# DIABETO_BLE.net
KiCad netlist of a schematic drawn in EAGLE
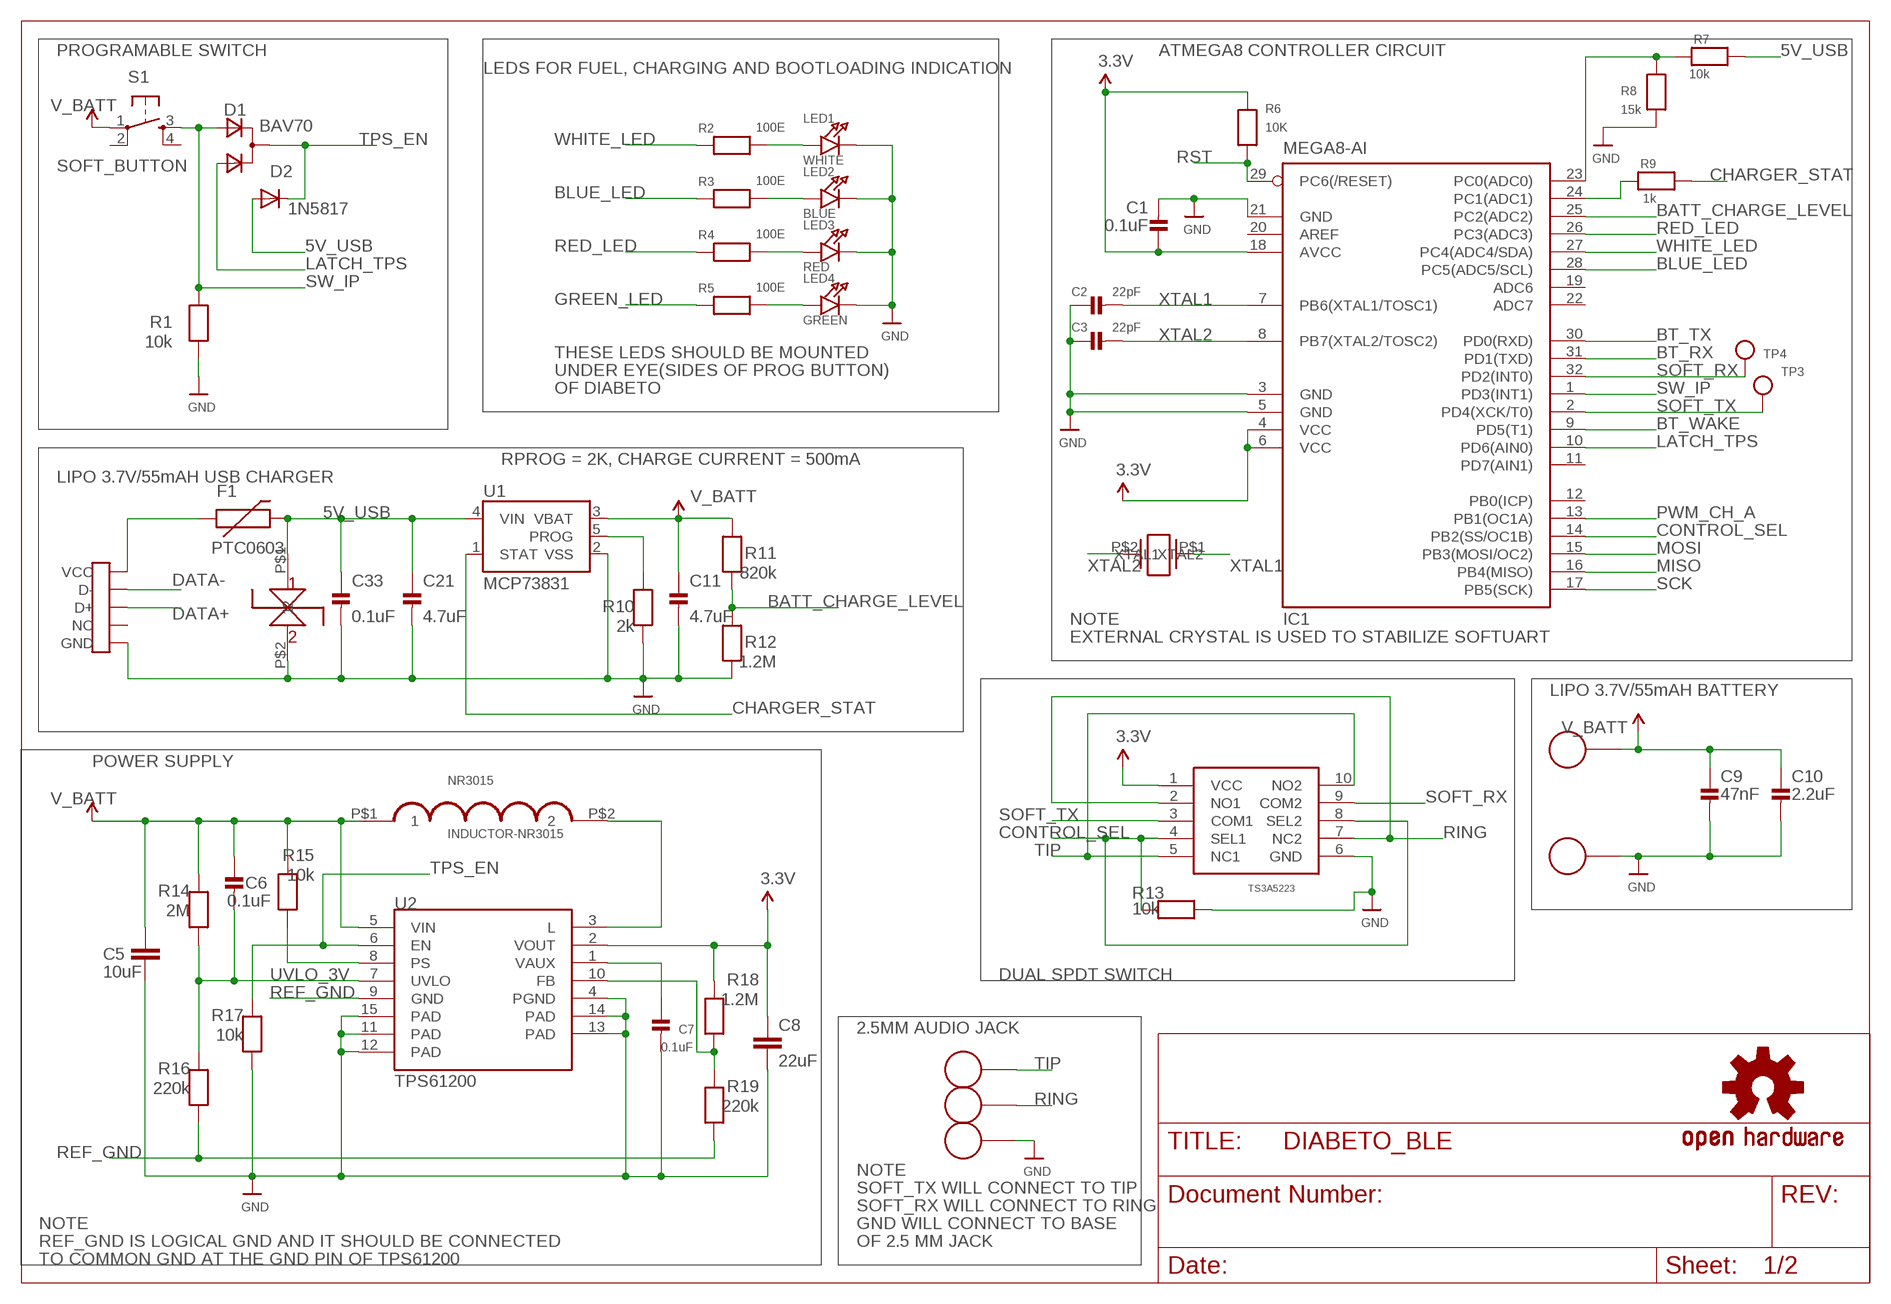
[diagram p0: schematic, sheet 1]
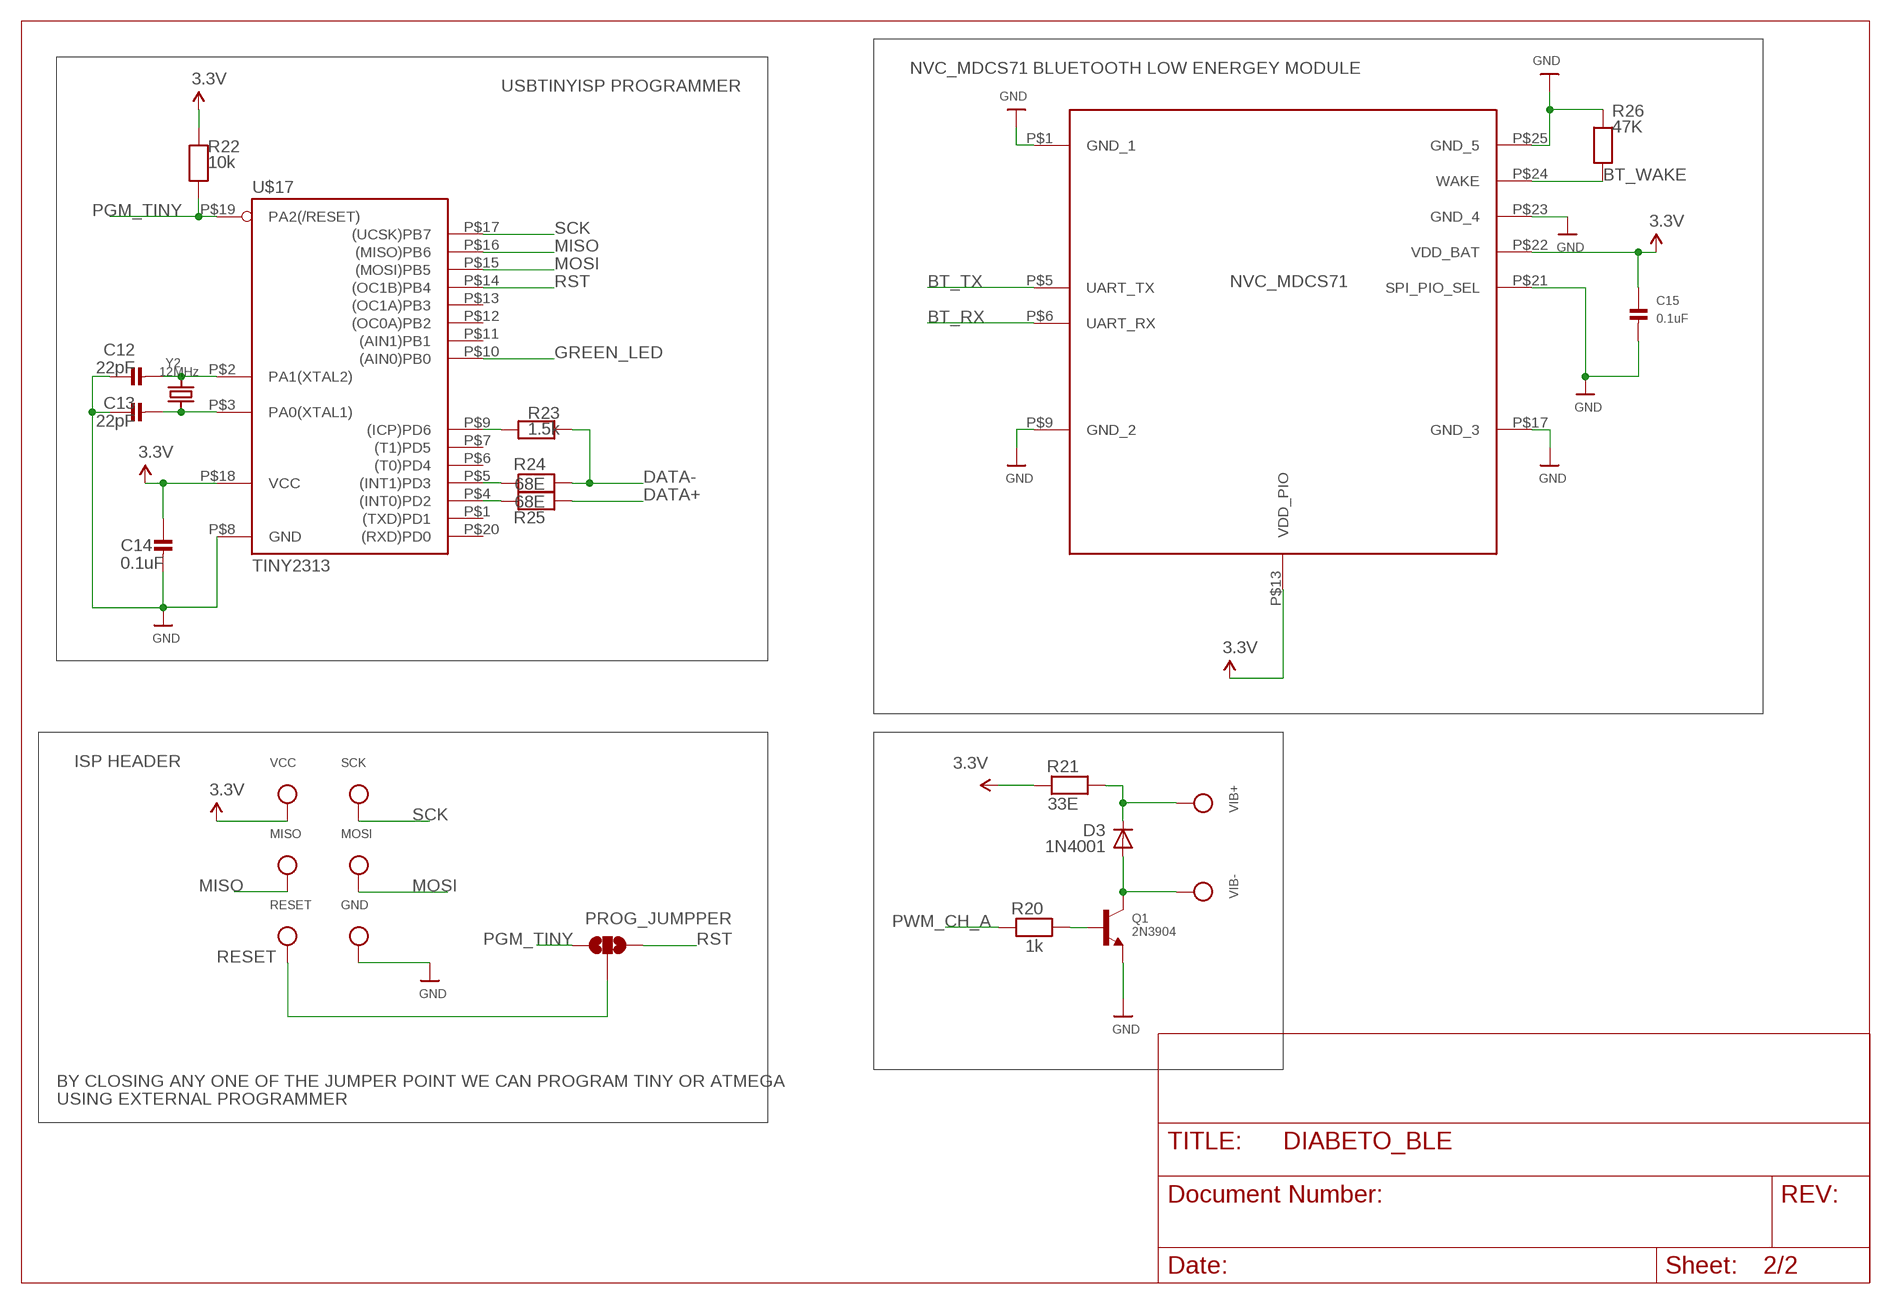
[diagram p1: schematic, sheet 2]

(export (version "E")
  (design (tool "Eeschema 10.0.6"))
  (components
    (comp (ref "C12")
      (value "22pF")
      (footprint "eagle-import:_0402")
      (libsource (lib "eagle-import") (part "CAP_CERAMIC_0402"))
    )
    (comp (ref "C13")
      (value "22pF")
      (footprint "eagle-import:_0402")
      (libsource (lib "eagle-import") (part "CAP_CERAMIC_0402"))
    )
    (comp (ref "C14")
      (value "0.1uF")
      (footprint "eagle-import:_0603")
      (libsource (lib "eagle-import") (part "CAP_CERAMIC_0603"))
    )
    (comp (ref "C15")
      (value "0.1uF")
      (footprint "eagle-import:_0603")
      (libsource (lib "eagle-import") (part "CAP_CERAMIC_0603"))
    )
    (comp (ref "D3")
      (value "1N4001")
      (footprint "eagle-import:SOD-323")
      (libsource (lib "eagle-import") (part "DIODESOD"))
    )
    (comp (ref "GND")
      (value "TESTPOINT0.1\"")
      (footprint "eagle-import:1X01_ROUND")
      (libsource (lib "eagle-import") (part "TESTPOINT0.1{dblquote}"))
    )
    (comp (ref "MISO")
      (value "TESTPOINTROUND1MM")
      (footprint "eagle-import:TESTPOINT_ROUND_1MM")
      (libsource (lib "eagle-import") (part "TESTPOINTROUND1MM"))
    )
    (comp (ref "MOSI")
      (value "TESTPOINTROUND1MM")
      (footprint "eagle-import:TESTPOINT_ROUND_1MM")
      (libsource (lib "eagle-import") (part "TESTPOINTROUND1MM"))
    )
    (comp (ref "PROG_JUMPPER")
      (value "SOLDERJUMPER_2WAY-OLDS")
      (footprint "eagle-import:SJ_3")
      (libsource (lib "eagle-import") (part "SOLDERJUMPER_2WAY-OLDS"))
    )
    (comp (ref "Q1")
      (value "2N3904")
      (footprint "eagle-import:SOT23-R")
      (libsource (lib "eagle-import") (part "TRANSISTOR_NPN"))
    )
    (comp (ref "R20")
      (value "1k")
      (footprint "eagle-import:_0603")
      (libsource (lib "eagle-import") (part "RESISTOR_0603"))
    )
    (comp (ref "R21")
      (value "33E")
      (footprint "eagle-import:_0603")
      (libsource (lib "eagle-import") (part "RESISTOR_0603"))
    )
    (comp (ref "R22")
      (value "10k")
      (footprint "eagle-import:_0603")
      (libsource (lib "eagle-import") (part "RESISTOR_0603"))
    )
    (comp (ref "R23")
      (value "1.5k")
      (footprint "eagle-import:_0603")
      (libsource (lib "eagle-import") (part "RESISTOR_0603"))
    )
    (comp (ref "R24")
      (value "68E")
      (footprint "eagle-import:_0603")
      (libsource (lib "eagle-import") (part "RESISTOR_0603"))
    )
    (comp (ref "R25")
      (value "68E")
      (footprint "eagle-import:_0603")
      (libsource (lib "eagle-import") (part "RESISTOR_0603"))
    )
    (comp (ref "R26")
      (value "47K")
      (footprint "eagle-import:_0603")
      (libsource (lib "eagle-import") (part "RESISTOR_0603"))
    )
    (comp (ref "RESET")
      (value "TESTPOINTROUND1MM")
      (footprint "eagle-import:TESTPOINT_ROUND_1MM")
      (libsource (lib "eagle-import") (part "TESTPOINTROUND1MM"))
    )
    (comp (ref "SCK")
      (value "TESTPOINTROUND1MM")
      (footprint "eagle-import:TESTPOINT_ROUND_1MM")
      (libsource (lib "eagle-import") (part "TESTPOINTROUND1MM"))
    )
    (comp (ref "U$9")
      (value "NVC_MDCS71SMD")
      (footprint "eagle-import:NVC_MDCS71")
      (libsource (lib "eagle-import") (part "NVC_MDCS71SMD"))
    )
    (comp (ref "U$17")
      (value "TINY2313")
      (footprint "eagle-import:MLF20")
      (libsource (lib "eagle-import") (part "TINY2313-M"))
    )
    (comp (ref "VCC")
      (value "TESTPOINT0.1\"")
      (footprint "eagle-import:1X01_ROUND")
      (libsource (lib "eagle-import") (part "TESTPOINT0.1{dblquote}"))
    )
    (comp (ref "VIB+")
      (value "TESTPOINTROUND0.5MM")
      (footprint "eagle-import:TESTPOINT_ROUND_0.5MM")
      (libsource (lib "eagle-import") (part "TESTPOINTROUND0.5MM"))
    )
    (comp (ref "VIB-")
      (value "TESTPOINTROUND0.5MM")
      (footprint "eagle-import:TESTPOINT_ROUND_0.5MM")
      (libsource (lib "eagle-import") (part "TESTPOINTROUND0.5MM"))
    )
    (comp (ref "Y2")
      (value "12MHz")
      (footprint "eagle-import:CRYSTAL_3.2X2.5")
      (libsource (lib "eagle-import") (part "CRYSTALTHIN"))
    )
    (comp (ref "BAT-")
      (value "TIP")
      (footprint "eagle-import:1X01_ROUND")
      (libsource (lib "eagle-import") (part "1X01_ROUND"))
    )
    (comp (ref "C1")
      (value "0.1uF")
      (footprint "eagle-import:_0603")
      (libsource (lib "eagle-import") (part "CAP_CERAMIC_0603"))
    )
    (comp (ref "C2")
      (value "22pF")
      (footprint "eagle-import:_0402")
      (libsource (lib "eagle-import") (part "CAP_CERAMIC_0402"))
    )
    (comp (ref "C3")
      (value "22pF")
      (footprint "eagle-import:_0402")
      (libsource (lib "eagle-import") (part "CAP_CERAMIC_0402"))
    )
    (comp (ref "C5")
      (value "10uF")
      (footprint "eagle-import:1206")
      (libsource (lib "eagle-import") (part "CAP1206"))
    )
    (comp (ref "C6")
      (value "0.1uF")
      (footprint "eagle-import:_0603")
      (libsource (lib "eagle-import") (part "CAP_CERAMIC_0603"))
    )
    (comp (ref "C7")
      (value "0.1uF")
      (footprint "eagle-import:_0603")
      (libsource (lib "eagle-import") (part "CAP_CERAMIC_0603"))
    )
    (comp (ref "C8")
      (value "22uF")
      (footprint "eagle-import:0805")
      (libsource (lib "eagle-import") (part "CAP0805"))
    )
    (comp (ref "C9")
      (value "47nF")
      (footprint "eagle-import:_0603")
      (libsource (lib "eagle-import") (part "CAP_CERAMIC_0603"))
    )
    (comp (ref "C10")
      (value "2.2uF")
      (footprint "eagle-import:_0603")
      (libsource (lib "eagle-import") (part "CAP_CERAMIC_0603"))
    )
    (comp (ref "C11")
      (value "4.7uF")
      (footprint "eagle-import:_0603")
      (libsource (lib "eagle-import") (part "CAP_CERAMIC_0603"))
    )
    (comp (ref "C21")
      (value "4.7uF")
      (footprint "eagle-import:_0603")
      (libsource (lib "eagle-import") (part "CAP_CERAMIC_0603"))
    )
    (comp (ref "C33")
      (value "0.1uF")
      (footprint "eagle-import:_0603")
      (libsource (lib "eagle-import") (part "CAP_CERAMIC_0603"))
    )
    (comp (ref "D1")
      (value "BAV70")
      (footprint "eagle-import:SOT-23")
      (libsource (lib "eagle-import") (part "D_2ASOT23"))
    )
    (comp (ref "D2")
      (value "1N5817")
      (footprint "eagle-import:SOD-123")
      (libsource (lib "eagle-import") (part "DIODESOD-123"))
    )
    (comp (ref "F1")
      (value "PTC0603")
      (footprint "eagle-import:0603")
      (libsource (lib "eagle-import") (part "PTC0603"))
    )
    (comp (ref "IC1")
      (value "MEGA8-AI")
      (footprint "eagle-import:TQFP32-08")
      (fields (field (name "MPN") "ATMEGA8-16AU"))
      (libsource (lib "eagle-import") (part "MEGA8-AI"))
    )
    (comp (ref "LED1")
      (value "WHITE")
      (footprint "eagle-import:CHIPLED_0603")
      (libsource (lib "eagle-import") (part "LED0603"))
    )
    (comp (ref "LED2")
      (value "BLUE")
      (footprint "eagle-import:CHIPLED_0603")
      (libsource (lib "eagle-import") (part "LED0603"))
    )
    (comp (ref "LED3")
      (value "RED")
      (footprint "eagle-import:CHIPLED_0603")
      (libsource (lib "eagle-import") (part "LED0603"))
    )
    (comp (ref "LED4")
      (value "GREEN")
      (footprint "eagle-import:CHIPLED_0603")
      (libsource (lib "eagle-import") (part "LED0603"))
    )
    (comp (ref "NR3015")
      (value "INDUCTOR-NR3015")
      (footprint "eagle-import:INDUCTOR-NR3015")
      (libsource (lib "eagle-import") (part "INDUCTOR-NR3015"))
    )
    (comp (ref "R1")
      (value "10k")
      (footprint "eagle-import:_0603")
      (libsource (lib "eagle-import") (part "RESISTOR_0603"))
    )
    (comp (ref "R2")
      (value "100E")
      (footprint "eagle-import:_0603")
      (libsource (lib "eagle-import") (part "RESISTOR_0603"))
    )
    (comp (ref "R3")
      (value "100E")
      (footprint "eagle-import:_0603")
      (libsource (lib "eagle-import") (part "RESISTOR_0603"))
    )
    (comp (ref "R4")
      (value "100E")
      (footprint "eagle-import:_0603")
      (libsource (lib "eagle-import") (part "RESISTOR_0603"))
    )
    (comp (ref "R5")
      (value "100E")
      (footprint "eagle-import:_0603")
      (libsource (lib "eagle-import") (part "RESISTOR_0603"))
    )
    (comp (ref "R6")
      (value "10K")
      (footprint "eagle-import:_0603")
      (libsource (lib "eagle-import") (part "RESISTOR_0603"))
    )
    (comp (ref "R7")
      (value "10k")
      (footprint "eagle-import:_0603")
      (libsource (lib "eagle-import") (part "RESISTOR_0603"))
    )
    (comp (ref "R8")
      (value "15k")
      (footprint "eagle-import:_0603")
      (libsource (lib "eagle-import") (part "RESISTOR_0603"))
    )
    (comp (ref "R9")
      (value "1k")
      (footprint "eagle-import:_0603")
      (libsource (lib "eagle-import") (part "RESISTOR_0603"))
    )
    (comp (ref "R10")
      (value "2k")
      (footprint "eagle-import:_0603")
      (libsource (lib "eagle-import") (part "RESISTOR_0603"))
    )
    (comp (ref "R11")
      (value "820k")
      (footprint "eagle-import:_0603")
      (libsource (lib "eagle-import") (part "RESISTOR_0603"))
    )
    (comp (ref "R12")
      (value "1.2M")
      (footprint "eagle-import:_0603")
      (libsource (lib "eagle-import") (part "RESISTOR_0603"))
    )
    (comp (ref "R13")
      (value "10k")
      (footprint "eagle-import:_0603")
      (libsource (lib "eagle-import") (part "RESISTOR_0603"))
    )
    (comp (ref "R14")
      (value "2M")
      (footprint "eagle-import:_0603")
      (libsource (lib "eagle-import") (part "RESISTOR_0603"))
    )
    (comp (ref "R15")
      (value "10k")
      (footprint "eagle-import:_0603")
      (libsource (lib "eagle-import") (part "RESISTOR_0603"))
    )
    (comp (ref "R16")
      (value "220k")
      (footprint "eagle-import:_0603")
      (libsource (lib "eagle-import") (part "RESISTOR_0603"))
    )
    (comp (ref "R17")
      (value "10k")
      (footprint "eagle-import:_0603")
      (libsource (lib "eagle-import") (part "RESISTOR_0603"))
    )
    (comp (ref "R18")
      (value "1.2M")
      (footprint "eagle-import:_0603")
      (libsource (lib "eagle-import") (part "RESISTOR_0603"))
    )
    (comp (ref "R19")
      (value "220k")
      (footprint "eagle-import:_0603")
      (libsource (lib "eagle-import") (part "RESISTOR_0603"))
    )
    (comp (ref "S1")
      (value "SOFT_BUTTON")
      (footprint "eagle-import:TACTILE_SWITCH_SMD")
      (libsource (lib "eagle-import") (part "TAC_SWITCHSMD"))
    )
    (comp (ref "TIP")
      (value "TIP")
      (footprint "eagle-import:1X01_ROUND")
      (libsource (lib "eagle-import") (part "1X01_ROUND"))
    )
    (comp (ref "TIP1")
      (value "TIP")
      (footprint "eagle-import:1X01_ROUND")
      (libsource (lib "eagle-import") (part "1X01_ROUND"))
    )
    (comp (ref "TP3")
      (value "TESTPOINTROUND1MM")
      (footprint "eagle-import:TESTPOINT_ROUND_1MM")
      (libsource (lib "eagle-import") (part "TESTPOINTROUND1MM"))
    )
    (comp (ref "TP4")
      (value "TESTPOINTROUND1MM")
      (footprint "eagle-import:TESTPOINT_ROUND_1MM")
      (libsource (lib "eagle-import") (part "TESTPOINTROUND1MM"))
    )
    (comp (ref "U$2")
      (value "MICRO_USB_DIABETOMICRO_USB_SMD")
      (footprint "eagle-import:MICRO_USB_DIABETO")
      (libsource (lib "eagle-import") (part "MICRO_USB_DIABETOMICRO_USB_SMD"))
    )
    (comp (ref "U$4")
      (value "TVS_DIODE")
      (footprint "eagle-import:0603")
      (libsource (lib "eagle-import") (part "TVS_DIODE"))
    )
    (comp (ref "U$20")
      (value "TS3A5223")
      (footprint "eagle-import:TS3A5223-QFN")
      (libsource (lib "eagle-import") (part "TS3A5223"))
    )
    (comp (ref "U$21")
      (value "OSHW-LOGOS")
      (footprint "eagle-import:OSHW-LOGO-S")
      (libsource (lib "eagle-import") (part "OSHW-LOGOS"))
    )
    (comp (ref "U$23")
      (value "8MHZ")
      (footprint "eagle-import:5X3.2_2PAD")
      (libsource (lib "eagle-import") (part "NX5032GA"))
    )
    (comp (ref "U$26")
      (value "1X01_ROUND")
      (footprint "eagle-import:1X01_ROUND")
      (libsource (lib "eagle-import") (part "1X01_ROUND"))
    )
    (comp (ref "U$28")
      (value "1X01_ROUND")
      (footprint "eagle-import:1X01_ROUND")
      (libsource (lib "eagle-import") (part "1X01_ROUND"))
    )
    (comp (ref "U1")
      (value "MCP73831")
      (footprint "eagle-import:SOT23-5")
      (libsource (lib "eagle-import") (part "MCP73831"))
    )
    (comp (ref "U2")
      (value "TPS61200")
      (footprint "eagle-import:QFN-10_PAD")
      (libsource (lib "eagle-import") (part "TPS61200"))
    )
  )
  (nets
    (net (code "1") (name "3.3V") (class "Default")
      (node (ref "C1") (pin "1") (pinfunction "P$1_1") (pintype "passive"))
      (node (ref "C14") (pin "1") (pinfunction "P$1_1") (pintype "passive"))
      (node (ref "C15") (pin "1") (pinfunction "P$1_1") (pintype "passive"))
      (node (ref "C8") (pin "1") (pinfunction "1_1") (pintype "passive"))
      (node (ref "IC1") (pin "18") (pinfunction "AVCC_18") (pintype "power_in"))
      (node (ref "IC1") (pin "4") (pinfunction "VCC_4") (pintype "power_in"))
      (node (ref "IC1") (pin "6") (pinfunction "VCC_6") (pintype "power_in"))
      (node (ref "R18") (pin "2") (pinfunction "2_2") (pintype "passive"))
      (node (ref "R21") (pin "1") (pinfunction "1_1") (pintype "passive"))
      (node (ref "R22") (pin "1") (pinfunction "1_1") (pintype "passive"))
      (node (ref "R6") (pin "2") (pinfunction "2_2") (pintype "passive"))
      (node (ref "U$17") (pin "P$18") (pinfunction "VCC_P$18") (pintype "power_in"))
      (node (ref "U$20") (pin "1") (pinfunction "VCC_1") (pintype "bidirectional"))
      (node (ref "U$9") (pin "P$13") (pinfunction "VDD_PIO_P$13") (pintype "bidirectional"))
      (node (ref "U$9") (pin "P$22") (pinfunction "VDD_BAT_P$22") (pintype "bidirectional"))
      (node (ref "U2") (pin "2") (pinfunction "VOUT_2") (pintype "passive"))
      (node (ref "VCC") (pin "1") (pinfunction "P$1_1") (pintype "bidirectional"))
    )
    (net (code "2") (name "5V_USB") (class "Default")
      (node (ref "C21") (pin "1") (pinfunction "P$1_1") (pintype "passive"))
      (node (ref "C33") (pin "1") (pinfunction "P$1_1") (pintype "passive"))
      (node (ref "D2") (pin "A") (pinfunction "A_A") (pintype "passive"))
      (node (ref "F1") (pin "2") (pinfunction "2_2") (pintype "bidirectional"))
      (node (ref "R7") (pin "1") (pinfunction "1_1") (pintype "passive"))
      (node (ref "U$4") (pin "P$1") (pinfunction "1_P$1") (pintype "bidirectional"))
      (node (ref "U1") (pin "4") (pinfunction "VIN_4") (pintype "power_in"))
    )
    (net (code "3") (name "BATT_CHARGE_LEVEL") (class "Default")
      (node (ref "IC1") (pin "25") (pinfunction "PC2(ADC2)_25") (pintype "bidirectional"))
      (node (ref "R11") (pin "1") (pinfunction "1_1") (pintype "passive"))
      (node (ref "R12") (pin "2") (pinfunction "2_2") (pintype "passive"))
    )
    (net (code "4") (name "BLUE_LED") (class "Default")
      (node (ref "IC1") (pin "28") (pinfunction "PC5(ADC5/SCL)_28") (pintype "bidirectional"))
      (node (ref "R3") (pin "2") (pinfunction "2_2") (pintype "passive"))
    )
    (net (code "5") (name "BT_RX") (class "Default")
      (node (ref "IC1") (pin "31") (pinfunction "PD1(TXD)_31") (pintype "bidirectional"))
      (node (ref "U$9") (pin "P$6") (pinfunction "UART_RX_P$6") (pintype "bidirectional"))
    )
    (net (code "6") (name "BT_TX") (class "Default")
      (node (ref "IC1") (pin "30") (pinfunction "PD0(RXD)_30") (pintype "bidirectional"))
      (node (ref "U$9") (pin "P$5") (pinfunction "UART_TX_P$5") (pintype "bidirectional"))
    )
    (net (code "7") (name "BT_WAKE") (class "Default")
      (node (ref "IC1") (pin "9") (pinfunction "PD5(T1)_9") (pintype "bidirectional"))
      (node (ref "R26") (pin "2") (pinfunction "2_2") (pintype "passive"))
      (node (ref "U$9") (pin "P$24") (pinfunction "WAKE_P$24") (pintype "bidirectional"))
    )
    (net (code "8") (name "CHARGER_STAT") (class "Default")
      (node (ref "R9") (pin "1") (pinfunction "1_1") (pintype "passive"))
      (node (ref "U1") (pin "1") (pinfunction "STAT_1") (pintype "output"))
    )
    (net (code "9") (name "CONTROL_SEL") (class "Default")
      (node (ref "IC1") (pin "14") (pinfunction "PB2(SS/OC1B)_14") (pintype "bidirectional"))
      (node (ref "R13") (pin "2") (pinfunction "2_2") (pintype "passive"))
      (node (ref "U$20") (pin "4") (pinfunction "SEL1_4") (pintype "bidirectional"))
      (node (ref "U$20") (pin "8") (pinfunction "SEL2_8") (pintype "bidirectional"))
    )
    (net (code "10") (name "DATA+") (class "Default")
      (node (ref "R25") (pin "2") (pinfunction "2_2") (pintype "passive"))
      (node (ref "U$2") (pin "P$3") (pinfunction "D+_P$3") (pintype "bidirectional"))
    )
    (net (code "11") (name "DATA-") (class "Default")
      (node (ref "R23") (pin "1") (pinfunction "1_1") (pintype "passive"))
      (node (ref "R24") (pin "2") (pinfunction "2_2") (pintype "passive"))
      (node (ref "U$2") (pin "P$6") (pinfunction "D-_P$6") (pintype "bidirectional"))
    )
    (net (code "12") (name "GND") (class "Default")
      (node (ref "BAT-") (pin "P$1") (pinfunction "1_P$1") (pintype "bidirectional"))
      (node (ref "C1") (pin "2") (pinfunction "P$2_2") (pintype "passive"))
      (node (ref "C10") (pin "2") (pinfunction "P$2_2") (pintype "passive"))
      (node (ref "C11") (pin "2") (pinfunction "P$2_2") (pintype "passive"))
      (node (ref "C12") (pin "1") (pinfunction "P$1_1") (pintype "passive"))
      (node (ref "C13") (pin "1") (pinfunction "P$1_1") (pintype "passive"))
      (node (ref "C14") (pin "2") (pinfunction "P$2_2") (pintype "passive"))
      (node (ref "C15") (pin "2") (pinfunction "P$2_2") (pintype "passive"))
      (node (ref "C2") (pin "1") (pinfunction "P$1_1") (pintype "passive"))
      (node (ref "C21") (pin "2") (pinfunction "P$2_2") (pintype "passive"))
      (node (ref "C3") (pin "1") (pinfunction "P$1_1") (pintype "passive"))
      (node (ref "C33") (pin "2") (pinfunction "P$2_2") (pintype "passive"))
      (node (ref "C5") (pin "2") (pinfunction "2_2") (pintype "passive"))
      (node (ref "C7") (pin "2") (pinfunction "P$2_2") (pintype "passive"))
      (node (ref "C8") (pin "2") (pinfunction "2_2") (pintype "passive"))
      (node (ref "C9") (pin "2") (pinfunction "P$2_2") (pintype "passive"))
      (node (ref "GND") (pin "1") (pinfunction "P$1_1") (pintype "bidirectional"))
      (node (ref "IC1") (pin "21") (pinfunction "GND_21") (pintype "power_in"))
      (node (ref "IC1") (pin "3") (pinfunction "GND_3") (pintype "power_in"))
      (node (ref "IC1") (pin "5") (pinfunction "GND_5") (pintype "power_in"))
      (node (ref "LED1") (pin "C") (pinfunction "C_C") (pintype "passive"))
      (node (ref "LED2") (pin "C") (pinfunction "C_C") (pintype "passive"))
      (node (ref "LED3") (pin "C") (pinfunction "C_C") (pintype "passive"))
      (node (ref "LED4") (pin "C") (pinfunction "C_C") (pintype "passive"))
      (node (ref "Q1") (pin "2") (pinfunction "E_2") (pintype "passive"))
      (node (ref "R1") (pin "1") (pinfunction "1_1") (pintype "passive"))
      (node (ref "R10") (pin "1") (pinfunction "1_1") (pintype "passive"))
      (node (ref "R12") (pin "1") (pinfunction "1_1") (pintype "passive"))
      (node (ref "R13") (pin "1") (pinfunction "1_1") (pintype "passive"))
      (node (ref "R17") (pin "1") (pinfunction "1_1") (pintype "passive"))
      (node (ref "R26") (pin "1") (pinfunction "1_1") (pintype "passive"))
      (node (ref "R8") (pin "2") (pinfunction "2_2") (pintype "passive"))
      (node (ref "U$17") (pin "P$8") (pinfunction "GND_P$8") (pintype "power_in"))
      (node (ref "U$2") (pin "P$5") (pinfunction "GND_P$5") (pintype "bidirectional"))
      (node (ref "U$20") (pin "6") (pinfunction "GND_6") (pintype "bidirectional"))
      (node (ref "U$28") (pin "P$1") (pinfunction "1_P$1") (pintype "bidirectional"))
      (node (ref "U$4") (pin "P$2") (pinfunction "2_P$2") (pintype "bidirectional"))
      (node (ref "U$9") (pin "P$1") (pinfunction "GND_1_P$1") (pintype "bidirectional"))
      (node (ref "U$9") (pin "P$17") (pinfunction "GND_3_P$17") (pintype "bidirectional"))
      (node (ref "U$9") (pin "P$21") (pinfunction "SPI_PIO_SEL_P$21") (pintype "bidirectional"))
      (node (ref "U$9") (pin "P$23") (pinfunction "GND_4_P$23") (pintype "bidirectional"))
      (node (ref "U$9") (pin "P$25") (pinfunction "GND_5_P$25") (pintype "bidirectional"))
      (node (ref "U$9") (pin "P$9") (pinfunction "GND_2_P$9") (pintype "bidirectional"))
      (node (ref "U1") (pin "2") (pinfunction "VSS_2") (pintype "power_in"))
      (node (ref "U2") (pin "11") (pinfunction "PAD_11") (pintype "power_in"))
      (node (ref "U2") (pin "12") (pinfunction "PAD_12") (pintype "power_in"))
      (node (ref "U2") (pin "13") (pinfunction "PAD_13") (pintype "power_in"))
      (node (ref "U2") (pin "14") (pinfunction "PAD_14") (pintype "power_in"))
      (node (ref "U2") (pin "15") (pinfunction "PAD_15") (pintype "power_in"))
      (node (ref "U2") (pin "4") (pinfunction "PGND_4") (pintype "power_in"))
    )
    (net (code "13") (name "GREEN_LED") (class "Default")
      (node (ref "R5") (pin "2") (pinfunction "2_2") (pintype "passive"))
      (node (ref "U$17") (pin "P$10") (pinfunction "(AIN0)PB0_P$10") (pintype "bidirectional"))
    )
    (net (code "14") (name "LATCH_TPS") (class "Default")
      (node (ref "D1") (pin "3") (pinfunction "A2_3") (pintype "passive"))
      (node (ref "IC1") (pin "10") (pinfunction "PD6(AIN0)_10") (pintype "bidirectional"))
    )
    (net (code "15") (name "MISO") (class "Default")
      (node (ref "IC1") (pin "16") (pinfunction "PB4(MISO)_16") (pintype "bidirectional"))
      (node (ref "MISO") (pin "P$1") (pinfunction "P$1_P$1") (pintype "bidirectional"))
      (node (ref "U$17") (pin "P$16") (pinfunction "(MISO)PB6_P$16") (pintype "bidirectional"))
    )
    (net (code "16") (name "MOSI") (class "Default")
      (node (ref "IC1") (pin "15") (pinfunction "PB3(MOSI/OC2)_15") (pintype "bidirectional"))
      (node (ref "MOSI") (pin "P$1") (pinfunction "P$1_P$1") (pintype "bidirectional"))
      (node (ref "U$17") (pin "P$15") (pinfunction "(MOSI)PB5_P$15") (pintype "bidirectional"))
    )
    (net (code "17") (name "Net-(C7-P$1)") (class "Default")
      (node (ref "C7") (pin "1") (pinfunction "P$1_1") (pintype "passive"))
      (node (ref "U2") (pin "1") (pinfunction "VAUX_1") (pintype "passive"))
    )
    (net (code "18") (name "Net-(C12-P$2)") (class "Default")
      (node (ref "C12") (pin "2") (pinfunction "P$2_2") (pintype "passive"))
      (node (ref "U$17") (pin "P$2") (pinfunction "PA1(XTAL2)_P$2") (pintype "bidirectional"))
      (node (ref "Y2") (pin "2") (pinfunction "2_2") (pintype "passive"))
    )
    (net (code "19") (name "Net-(C13-P$2)") (class "Default")
      (node (ref "C13") (pin "2") (pinfunction "P$2_2") (pintype "passive"))
      (node (ref "U$17") (pin "P$3") (pinfunction "PA0(XTAL1)_P$3") (pintype "bidirectional"))
      (node (ref "Y2") (pin "1") (pinfunction "1_1") (pintype "passive"))
    )
    (net (code "20") (name "Net-(D3-A)") (class "Default")
      (node (ref "D3") (pin "2") (pinfunction "A_2") (pintype "passive"))
      (node (ref "Q1") (pin "3") (pinfunction "C_3") (pintype "passive"))
      (node (ref "VIB-") (pin "P$1") (pinfunction "P$1_P$1") (pintype "bidirectional"))
    )
    (net (code "21") (name "Net-(D3-C)") (class "Default")
      (node (ref "D3") (pin "1") (pinfunction "C_1") (pintype "passive"))
      (node (ref "R21") (pin "2") (pinfunction "2_2") (pintype "passive"))
      (node (ref "VIB+") (pin "P$1") (pinfunction "P$1_P$1") (pintype "bidirectional"))
    )
    (net (code "22") (name "Net-(IC1-PC0(ADC0))") (class "Default")
      (node (ref "IC1") (pin "23") (pinfunction "PC0(ADC0)_23") (pintype "bidirectional"))
      (node (ref "R7") (pin "2") (pinfunction "2_2") (pintype "passive"))
      (node (ref "R8") (pin "1") (pinfunction "1_1") (pintype "passive"))
    )
    (net (code "23") (name "Net-(IC1-PC1(ADC1))") (class "Default")
      (node (ref "IC1") (pin "24") (pinfunction "PC1(ADC1)_24") (pintype "bidirectional"))
      (node (ref "R9") (pin "2") (pinfunction "2_2") (pintype "passive"))
    )
    (net (code "24") (name "Net-(LED1-PadA)") (class "Default")
      (node (ref "LED1") (pin "A") (pinfunction "A_A") (pintype "passive"))
      (node (ref "R2") (pin "1") (pinfunction "1_1") (pintype "passive"))
    )
    (net (code "25") (name "Net-(LED2-PadA)") (class "Default")
      (node (ref "LED2") (pin "A") (pinfunction "A_A") (pintype "passive"))
      (node (ref "R3") (pin "1") (pinfunction "1_1") (pintype "passive"))
    )
    (net (code "26") (name "Net-(LED3-PadA)") (class "Default")
      (node (ref "LED3") (pin "A") (pinfunction "A_A") (pintype "passive"))
      (node (ref "R4") (pin "1") (pinfunction "1_1") (pintype "passive"))
    )
    (net (code "27") (name "Net-(LED4-PadA)") (class "Default")
      (node (ref "LED4") (pin "A") (pinfunction "A_A") (pintype "passive"))
      (node (ref "R5") (pin "1") (pinfunction "1_1") (pintype "passive"))
    )
    (net (code "28") (name "Net-(NR3015-2)") (class "Default")
      (node (ref "NR3015") (pin "P$2") (pinfunction "2_P$2") (pintype "bidirectional"))
      (node (ref "U2") (pin "3") (pinfunction "L_3") (pintype "passive"))
    )
    (net (code "29") (name "Net-(Q1-B)") (class "Default")
      (node (ref "Q1") (pin "1") (pinfunction "B_1") (pintype "passive"))
      (node (ref "R20") (pin "2") (pinfunction "2_2") (pintype "passive"))
    )
    (net (code "30") (name "Net-(U$2-VCC)") (class "Default")
      (node (ref "F1") (pin "1") (pinfunction "1_1") (pintype "bidirectional"))
      (node (ref "U$2") (pin "P$7") (pinfunction "VCC_P$7") (pintype "bidirectional"))
    )
    (net (code "31") (name "Net-(U$17-(ICP)PD6)") (class "Default")
      (node (ref "R23") (pin "2") (pinfunction "2_2") (pintype "passive"))
      (node (ref "U$17") (pin "P$9") (pinfunction "(ICP)PD6_P$9") (pintype "bidirectional"))
    )
    (net (code "32") (name "Net-(U$17-(INT0)PD2)") (class "Default")
      (node (ref "R25") (pin "1") (pinfunction "1_1") (pintype "passive"))
      (node (ref "U$17") (pin "P$4") (pinfunction "(INT0)PD2_P$4") (pintype "bidirectional"))
    )
    (net (code "33") (name "Net-(U$17-(INT1)PD3)") (class "Default")
      (node (ref "R24") (pin "1") (pinfunction "1_1") (pintype "passive"))
      (node (ref "U$17") (pin "P$5") (pinfunction "(INT1)PD3_P$5") (pintype "bidirectional"))
    )
    (net (code "34") (name "Net-(U1-PROG)") (class "Default")
      (node (ref "R10") (pin "2") (pinfunction "2_2") (pintype "passive"))
      (node (ref "U1") (pin "5") (pinfunction "PROG_5") (pintype "input"))
    )
    (net (code "35") (name "Net-(U2-FB)") (class "Default")
      (node (ref "R18") (pin "1") (pinfunction "1_1") (pintype "passive"))
      (node (ref "R19") (pin "2") (pinfunction "2_2") (pintype "passive"))
      (node (ref "U2") (pin "10") (pinfunction "FB_10") (pintype "passive"))
    )
    (net (code "36") (name "Net-(U2-PS)") (class "Default")
      (node (ref "R15") (pin "1") (pinfunction "1_1") (pintype "passive"))
      (node (ref "U2") (pin "8") (pinfunction "PS_8") (pintype "input"))
    )
    (net (code "37") (name "PGM_TINY") (class "Default")
      (node (ref "PROG_JUMPPER") (pin "1") (pinfunction "1_1") (pintype "passive"))
      (node (ref "R22") (pin "2") (pinfunction "2_2") (pintype "passive"))
      (node (ref "U$17") (pin "P$19") (pinfunction "PA2(/RESET)_P$19") (pintype "input"))
    )
    (net (code "38") (name "PWM_CH_A") (class "Default")
      (node (ref "IC1") (pin "13") (pinfunction "PB1(OC1A)_13") (pintype "bidirectional"))
      (node (ref "R20") (pin "1") (pinfunction "1_1") (pintype "passive"))
    )
    (net (code "39") (name "RED_LED") (class "Default")
      (node (ref "IC1") (pin "26") (pinfunction "PC3(ADC3)_26") (pintype "bidirectional"))
      (node (ref "R4") (pin "2") (pinfunction "2_2") (pintype "passive"))
    )
    (net (code "40") (name "REF_GND") (class "Default")
      (node (ref "R16") (pin "1") (pinfunction "1_1") (pintype "passive"))
      (node (ref "R19") (pin "1") (pinfunction "1_1") (pintype "passive"))
      (node (ref "U2") (pin "9") (pinfunction "GND_9") (pintype "power_in"))
    )
    (net (code "41") (name "RESET") (class "Default")
      (node (ref "PROG_JUMPPER") (pin "2") (pinfunction "2_2") (pintype "passive"))
      (node (ref "RESET") (pin "P$1") (pinfunction "P$1_P$1") (pintype "bidirectional"))
    )
    (net (code "42") (name "RING") (class "Default")
      (node (ref "U$20") (pin "2") (pinfunction "NO1_2") (pintype "bidirectional"))
      (node (ref "U$20") (pin "7") (pinfunction "NC2_7") (pintype "bidirectional"))
      (node (ref "U$26") (pin "P$1") (pinfunction "1_P$1") (pintype "bidirectional"))
    )
    (net (code "43") (name "RST") (class "Default")
      (node (ref "IC1") (pin "29") (pinfunction "PC6(/RESET)_29") (pintype "bidirectional"))
      (node (ref "PROG_JUMPPER") (pin "3") (pinfunction "3_3") (pintype "passive"))
      (node (ref "R6") (pin "1") (pinfunction "1_1") (pintype "passive"))
      (node (ref "U$17") (pin "P$14") (pinfunction "(OC1B)PB4_P$14") (pintype "bidirectional"))
    )
    (net (code "44") (name "SCK") (class "Default")
      (node (ref "IC1") (pin "17") (pinfunction "PB5(SCK)_17") (pintype "bidirectional"))
      (node (ref "SCK") (pin "P$1") (pinfunction "P$1_P$1") (pintype "bidirectional"))
      (node (ref "U$17") (pin "P$17") (pinfunction "(UCSK)PB7_P$17") (pintype "bidirectional"))
    )
    (net (code "45") (name "SOFT_RX") (class "Default")
      (node (ref "IC1") (pin "32") (pinfunction "PD2(INT0)_32") (pintype "bidirectional"))
      (node (ref "TP4") (pin "P$1") (pinfunction "P$1_P$1") (pintype "bidirectional"))
      (node (ref "U$20") (pin "9") (pinfunction "COM2_9") (pintype "bidirectional"))
    )
    (net (code "46") (name "SOFT_TX") (class "Default")
      (node (ref "IC1") (pin "2") (pinfunction "PD4(XCK/T0)_2") (pintype "bidirectional"))
      (node (ref "TP3") (pin "P$1") (pinfunction "P$1_P$1") (pintype "bidirectional"))
      (node (ref "U$20") (pin "3") (pinfunction "COM1_3") (pintype "bidirectional"))
    )
    (net (code "47") (name "SW_IP") (class "Default")
      (node (ref "D1") (pin "2") (pinfunction "A1_2") (pintype "passive"))
      (node (ref "IC1") (pin "1") (pinfunction "PD3(INT1)_1") (pintype "bidirectional"))
      (node (ref "R1") (pin "2") (pinfunction "2_2") (pintype "passive"))
      (node (ref "S1") (pin "3") (pinfunction "3_3") (pintype "passive"))
    )
    (net (code "48") (name "TIP") (class "Default")
      (node (ref "TIP") (pin "P$1") (pinfunction "1_P$1") (pintype "bidirectional"))
      (node (ref "U$20") (pin "10") (pinfunction "NO2_10") (pintype "bidirectional"))
      (node (ref "U$20") (pin "5") (pinfunction "NC1_5") (pintype "bidirectional"))
    )
    (net (code "49") (name "TPS_EN") (class "Default")
      (node (ref "D1") (pin "1") (pinfunction "C_1") (pintype "passive"))
      (node (ref "D2") (pin "C") (pinfunction "C_C") (pintype "passive"))
      (node (ref "R17") (pin "2") (pinfunction "2_2") (pintype "passive"))
      (node (ref "U2") (pin "6") (pinfunction "EN_6") (pintype "input"))
    )
    (net (code "50") (name "UVLO_3V") (class "Default")
      (node (ref "C6") (pin "2") (pinfunction "P$2_2") (pintype "passive"))
      (node (ref "R14") (pin "1") (pinfunction "1_1") (pintype "passive"))
      (node (ref "R16") (pin "2") (pinfunction "2_2") (pintype "passive"))
      (node (ref "U2") (pin "7") (pinfunction "UVLO_7") (pintype "passive"))
    )
    (net (code "51") (name "V_BATT") (class "Default")
      (node (ref "C10") (pin "1") (pinfunction "P$1_1") (pintype "passive"))
      (node (ref "C11") (pin "1") (pinfunction "P$1_1") (pintype "passive"))
      (node (ref "C5") (pin "1") (pinfunction "1_1") (pintype "passive"))
      (node (ref "C6") (pin "1") (pinfunction "P$1_1") (pintype "passive"))
      (node (ref "C9") (pin "1") (pinfunction "P$1_1") (pintype "passive"))
      (node (ref "NR3015") (pin "P$1") (pinfunction "1_P$1") (pintype "bidirectional"))
      (node (ref "R11") (pin "2") (pinfunction "2_2") (pintype "passive"))
      (node (ref "R14") (pin "2") (pinfunction "2_2") (pintype "passive"))
      (node (ref "R15") (pin "2") (pinfunction "2_2") (pintype "passive"))
      (node (ref "S1") (pin "1") (pinfunction "1_1") (pintype "passive"))
      (node (ref "TIP1") (pin "P$1") (pinfunction "1_P$1") (pintype "bidirectional"))
      (node (ref "U1") (pin "3") (pinfunction "VBAT_3") (pintype "power_in"))
      (node (ref "U2") (pin "5") (pinfunction "VIN_5") (pintype "power_in"))
    )
    (net (code "52") (name "WHITE_LED") (class "Default")
      (node (ref "IC1") (pin "27") (pinfunction "PC4(ADC4/SDA)_27") (pintype "bidirectional"))
      (node (ref "R2") (pin "2") (pinfunction "2_2") (pintype "passive"))
    )
    (net (code "53") (name "XTAL1") (class "Default")
      (node (ref "C2") (pin "2") (pinfunction "P$2_2") (pintype "passive"))
      (node (ref "IC1") (pin "7") (pinfunction "PB6(XTAL1/TOSC1)_7") (pintype "bidirectional"))
      (node (ref "U$23") (pin "P$1") (pinfunction "XTAL1_P$1") (pintype "bidirectional"))
    )
    (net (code "54") (name "XTAL2") (class "Default")
      (node (ref "C3") (pin "2") (pinfunction "P$2_2") (pintype "passive"))
      (node (ref "IC1") (pin "8") (pinfunction "PB7(XTAL2/TOSC2)_8") (pintype "bidirectional"))
      (node (ref "U$23") (pin "P$2") (pinfunction "XTAL2_P$2") (pintype "bidirectional"))
    )
    (net (code "55") (name "unconnected-(IC1-ADC6-Pad19)") (class "Default")
      (node (ref "IC1") (pin "19") (pinfunction "ADC6_19") (pintype "bidirectional"))
    )
    (net (code "56") (name "unconnected-(IC1-ADC7-Pad22)") (class "Default")
      (node (ref "IC1") (pin "22") (pinfunction "ADC7_22") (pintype "bidirectional"))
    )
    (net (code "57") (name "unconnected-(IC1-AREF-Pad20)") (class "Default")
      (node (ref "IC1") (pin "20") (pinfunction "AREF_20") (pintype "passive"))
    )
    (net (code "58") (name "unconnected-(IC1-PB0(ICP)-Pad12)") (class "Default")
      (node (ref "IC1") (pin "12") (pinfunction "PB0(ICP)_12") (pintype "bidirectional"))
    )
    (net (code "59") (name "unconnected-(IC1-PD7(AIN1)-Pad11)") (class "Default")
      (node (ref "IC1") (pin "11") (pinfunction "PD7(AIN1)_11") (pintype "bidirectional"))
    )
    (net (code "60") (name "unconnected-(S1-Pad2)") (class "Default")
      (node (ref "S1") (pin "2") (pinfunction "2_2") (pintype "passive"))
    )
    (net (code "61") (name "unconnected-(S1-Pad4)") (class "Default")
      (node (ref "S1") (pin "4") (pinfunction "4_4") (pintype "passive"))
    )
    (net (code "62") (name "unconnected-(U$2-NC-PadP$4)") (class "Default")
      (node (ref "U$2") (pin "P$4") (pinfunction "NC_P$4") (pintype "bidirectional"))
    )
    (net (code "63") (name "unconnected-(U$17-(AIN1)PB1-PadP$11)") (class "Default")
      (node (ref "U$17") (pin "P$11") (pinfunction "(AIN1)PB1_P$11") (pintype "bidirectional"))
    )
    (net (code "64") (name "unconnected-(U$17-(OC0A)PB2-PadP$12)") (class "Default")
      (node (ref "U$17") (pin "P$12") (pinfunction "(OC0A)PB2_P$12") (pintype "bidirectional"))
    )
    (net (code "65") (name "unconnected-(U$17-(OC1A)PB3-PadP$13)") (class "Default")
      (node (ref "U$17") (pin "P$13") (pinfunction "(OC1A)PB3_P$13") (pintype "bidirectional"))
    )
    (net (code "66") (name "unconnected-(U$17-(RXD)PD0-PadP$20)") (class "Default")
      (node (ref "U$17") (pin "P$20") (pinfunction "(RXD)PD0_P$20") (pintype "bidirectional"))
    )
    (net (code "67") (name "unconnected-(U$17-(T0)PD4-PadP$6)") (class "Default")
      (node (ref "U$17") (pin "P$6") (pinfunction "(T0)PD4_P$6") (pintype "bidirectional"))
    )
    (net (code "68") (name "unconnected-(U$17-(T1)PD5-PadP$7)") (class "Default")
      (node (ref "U$17") (pin "P$7") (pinfunction "(T1)PD5_P$7") (pintype "bidirectional"))
    )
    (net (code "69") (name "unconnected-(U$17-(TXD)PD1-PadP$1)") (class "Default")
      (node (ref "U$17") (pin "P$1") (pinfunction "(TXD)PD1_P$1") (pintype "bidirectional"))
    )
  )
)
